# SD_USB_FMU_REV_1A.net
KiCad netlist of a schematic drawn in Altium Designer
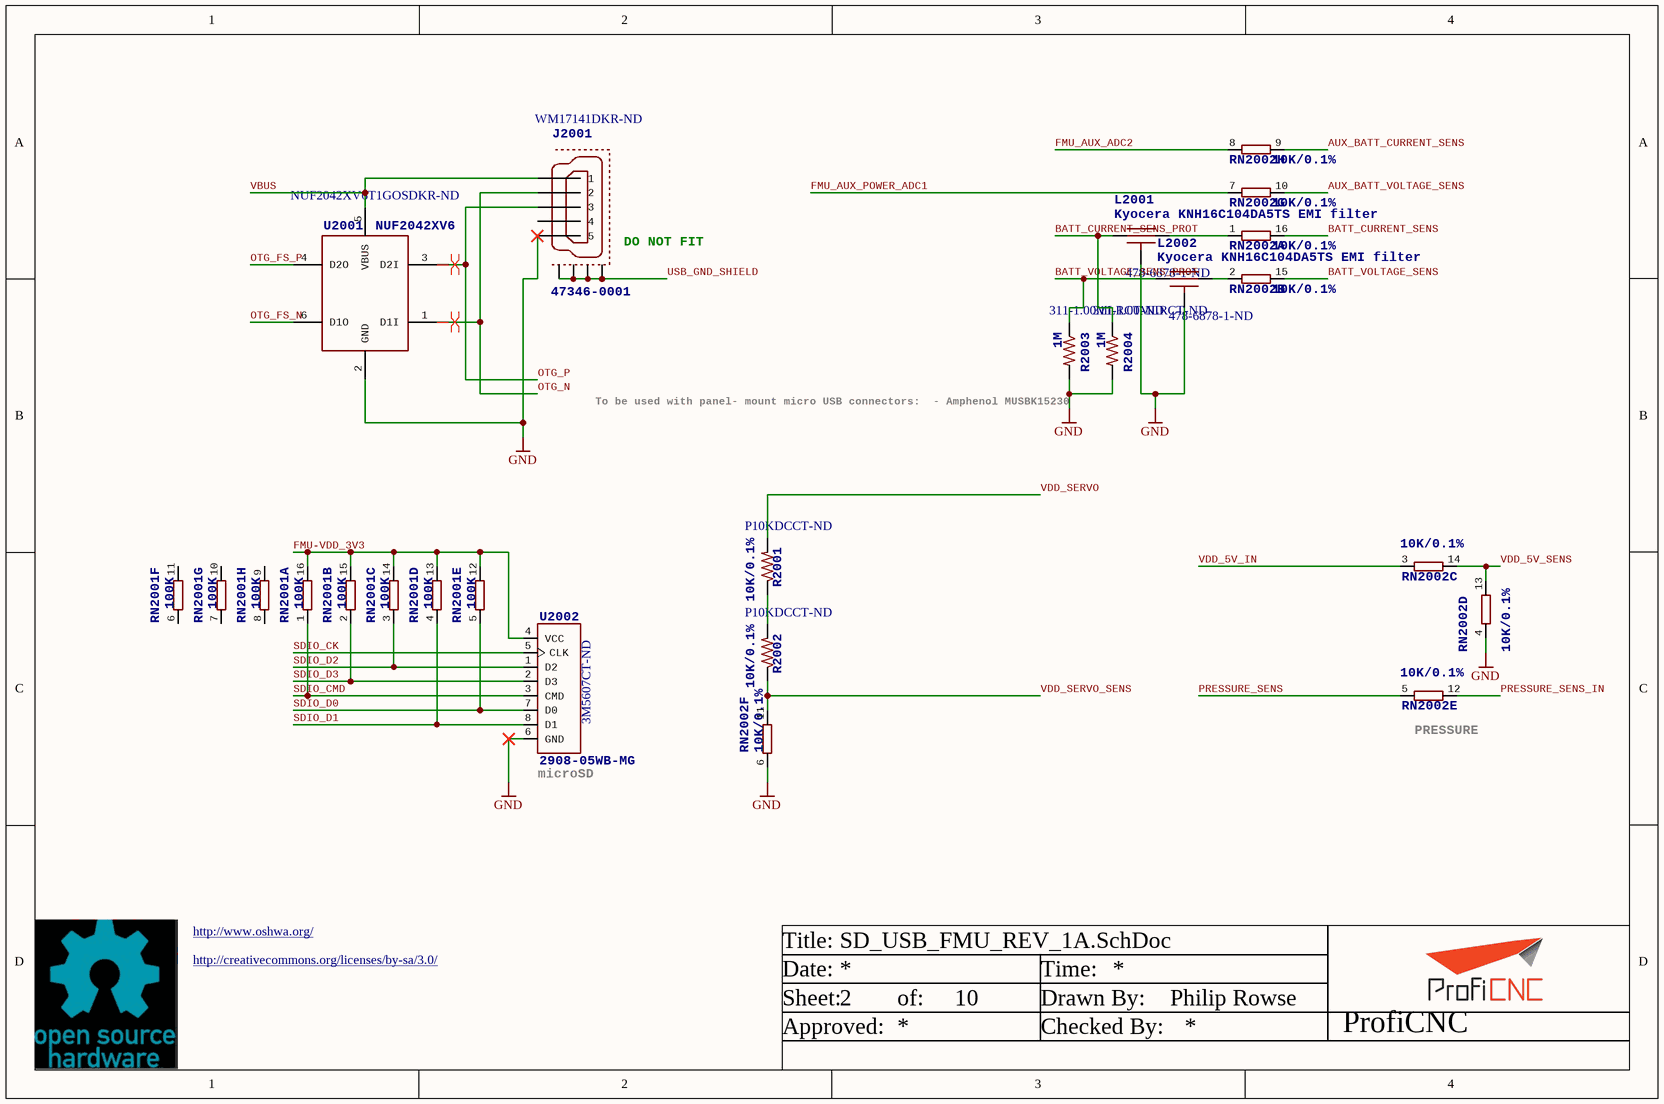
[diagram p0: SD_USB_FMU_REV_1A.SchDoc]

(export (version "E")
  (design (tool "Eeschema 10.0.6"))
  (components
    (comp (ref "J2001")
      (value "47346-0001")
      (footprint "MOLEX-47346-0001")
      (description "MICRO USB B, BOTTOM MOUNT")
      (fields
        (field (name "SUPPLIER PART NUMBER 1") "WM17141DKR-ND")
        (field (name "3DR_PARTNO") "ECM0486")
        (field (name "PARTNO") "0473460001")
      )
      (libsource (lib "pixhawk2") (part "MOLEX-47346-0001"))
    )
    (comp (ref "L2001")
      (value "Kyocera KNH16C104DA5TS EMI filter")
      (footprint "KYOCERA-KNH16-DA")
      (description "FILTER CAP 0.1UF 2A 25V 0603")
      (fields
        (field (name "SUPPLIER PART NUMBER 1") "478-6878-1-ND")
        (field (name "3DR_PARTNO") "ECM0719")
        (field (name "PARTNO") "KNH16C104DA5TS")
      )
      (libsource (lib "pixhawk2") (part "KNH16C104DA5TS"))
    )
    (comp (ref "L2002")
      (value "Kyocera KNH16C104DA5TS EMI filter")
      (footprint "KYOCERA-KNH16-DA")
      (description "FILTER CAP 0.1UF 2A 25V 0603")
      (fields
        (field (name "SUPPLIER PART NUMBER 1") "478-6878-1-ND")
        (field (name "3DR_PARTNO") "ECM0719")
        (field (name "PARTNO") "KNH16C104DA5TS")
      )
      (libsource (lib "pixhawk2") (part "KNH16C104DA5TS"))
    )
    (comp (ref "R2001")
      (value "10K/0.1%")
      (footprint "0402-RES")
      (description "RES 10K OHM 1/16W .1% 0402 SMD")
      (fields
        (field (name "SUPPLIER PART NUMBER 1") "P10KDCCT-ND")
        (field (name "3DR_PARTNO") "ECM0810")
        (field (name "PARTNO") "ERA-2AEB103X")
      )
      (libsource (lib "pixhawk2") (part "RESISTOR0402-RES"))
    )
    (comp (ref "R2002")
      (value "10K/0.1%")
      (footprint "0402-RES")
      (description "RES 10K OHM 1/16W .1% 0402 SMD")
      (fields
        (field (name "SUPPLIER PART NUMBER 1") "P10KDCCT-ND")
        (field (name "3DR_PARTNO") "ECM0810")
        (field (name "PARTNO") "ERA-2AEB103X")
      )
      (libsource (lib "pixhawk2") (part "RESISTOR0402-RES"))
    )
    (comp (ref "R2003")
      (value "1M")
      (footprint "0402-RES")
      (description "RES 1M OHM 1/16W 1% 0402 SMD")
      (fields
        (field (name "PARTNO") "RC0402FR-071ML")
        (field (name "SUPPLIER PART NUMBER 1") "311-1.00MLRCT-ND")
        (field (name "3DR_PARTNO") "ECM0806")
      )
      (libsource (lib "pixhawk2") (part "RESISTOR0402-RES"))
    )
    (comp (ref "R2004")
      (value "1M")
      (footprint "0402-RES")
      (description "RES 1M OHM 1/16W 1% 0402 SMD")
      (fields
        (field (name "PARTNO") "RC0402FR-071ML")
        (field (name "SUPPLIER PART NUMBER 1") "311-1.00MLRCT-ND")
        (field (name "3DR_PARTNO") "ECM0806")
      )
      (libsource (lib "pixhawk2") (part "RESISTOR0402-RES"))
    )
    (comp (ref "RN2001")
      (value "100K")
      (footprint "EXB2HV")
      (description "RES ARRAY 100K OHM 8 RES 1506")
      (fields (field (name "PARTNO") "EXB-2HV104JV") (field (name "3DR_PARTNO") "ECM0101"))
      (libsource (lib "pixhawk2") (part "8R-NEXB2HV-100K"))
    )
    (comp (ref "RN2002")
      (value "10K/0.1%")
      (footprint "EXB2HV")
      (description "RES ARRAY 10K OHM 8 RES 1506")
      (fields (field (name "PARTNO") "EXB-2HV103JV") (field (name "3DR_PARTNO") "ECM0546"))
      (libsource (lib "pixhawk2") (part "8R-NEXB2HV-10K"))
    )
    (comp (ref "U2001")
      (value "NUF2042XV6")
      (footprint "SOT563-6")
      (description "IC FILTER USB ESD PROTECT SOT363")
      (fields
        (field (name "PARTNO") "NUF2042XV6T1G")
        (field (name "SUPPLIER PART NUMBER 1") "NUF2042XV6T1GOSDKR-ND")
        (field (name "3DR_PARTNO") "ECM0836")
      )
      (libsource (lib "pixhawk2") (part "NUF2042XV6"))
    )
    (comp (ref "U2002")
      (value "2908-05WB-MG")
      (footprint "MICROSD")
      (description "CONN MICRO SD CARD PUSH-PUSH R/A")
      (fields (field (name "SUPPLIER PART NUMBER 1") "3M5607CT-ND") (field (name "3DR_PARTNO") "ECM0485"))
      (libsource (lib "baseboard") (part "MICROSDSDI"))
    )
  )
  (nets
    (net (code "1") (name "/AUX_BATT_CURRENT_SENS") (class "Default")
      (node (ref "RN2002") (pin "9") (pinfunction "2_9") (pintype "passive"))
    )
    (net (code "2") (name "/AUX_BATT_VOLTAGE_SENS") (class "Default")
      (node (ref "RN2002") (pin "10") (pinfunction "2_10") (pintype "passive"))
    )
    (net (code "3") (name "/BATT_CURRENT_SENS") (class "Default")
      (node (ref "RN2002") (pin "16") (pinfunction "2_16") (pintype "passive"))
    )
    (net (code "4") (name "/BATT_CURRENT_SENS_PROT") (class "Default")
      (node (ref "L2001") (pin "P$1") (pinfunction "P$1_P$1") (pintype "passive"))
      (node (ref "R2004") (pin "P$1") (pinfunction "1_P$1") (pintype "passive"))
    )
    (net (code "5") (name "/BATT_VOLTAGE_SENS") (class "Default")
      (node (ref "RN2002") (pin "15") (pinfunction "2_15") (pintype "passive"))
    )
    (net (code "6") (name "/BATT_VOLTAGE_SENS_PROT") (class "Default")
      (node (ref "L2002") (pin "P$1") (pinfunction "P$1_P$1") (pintype "passive"))
      (node (ref "R2003") (pin "P$1") (pinfunction "1_P$1") (pintype "passive"))
    )
    (net (code "7") (name "/FMU-VDD_3V3") (class "Default")
      (node (ref "RN2001") (pin "12") (pinfunction "2_12") (pintype "passive"))
      (node (ref "RN2001") (pin "13") (pinfunction "2_13") (pintype "passive"))
      (node (ref "RN2001") (pin "14") (pinfunction "2_14") (pintype "passive"))
      (node (ref "RN2001") (pin "15") (pinfunction "2_15") (pintype "passive"))
      (node (ref "RN2001") (pin "16") (pinfunction "2_16") (pintype "passive"))
      (node (ref "U2002") (pin "4") (pinfunction "VCC_4") (pintype "passive"))
    )
    (net (code "8") (name "/FMU_AUX_ADC2") (class "Default")
      (node (ref "RN2002") (pin "8") (pinfunction "1_8") (pintype "passive"))
    )
    (net (code "9") (name "/FMU_AUX_POWER_ADC1") (class "Default")
      (node (ref "RN2002") (pin "7") (pinfunction "1_7") (pintype "passive"))
    )
    (net (code "10") (name "/OTG_FS_N") (class "Default")
      (node (ref "U2001") (pin "6") (pinfunction "D1O_6") (pintype "passive"))
    )
    (net (code "11") (name "/OTG_FS_P") (class "Default")
      (node (ref "U2001") (pin "4") (pinfunction "D2O_4") (pintype "passive"))
    )
    (net (code "12") (name "/OTG_N") (class "Default")
      (node (ref "J2001") (pin "D-") (pinfunction "2_D-") (pintype "passive"))
      (node (ref "U2001") (pin "1") (pinfunction "D1I_1") (pintype "passive"))
    )
    (net (code "13") (name "/OTG_P") (class "Default")
      (node (ref "J2001") (pin "D+") (pinfunction "3_D+") (pintype "passive"))
      (node (ref "U2001") (pin "3") (pinfunction "D2I_3") (pintype "passive"))
    )
    (net (code "14") (name "/PRESSURE_SENS") (class "Default")
      (node (ref "RN2002") (pin "5") (pinfunction "1_5") (pintype "passive"))
    )
    (net (code "15") (name "/PRESSURE_SENS_IN") (class "Default")
      (node (ref "RN2002") (pin "12") (pinfunction "2_12") (pintype "passive"))
    )
    (net (code "16") (name "/SDIO_CK") (class "Default")
      (node (ref "U2002") (pin "5") (pinfunction "CLK_5") (pintype "passive"))
    )
    (net (code "17") (name "/SDIO_CMD") (class "Default")
      (node (ref "RN2001") (pin "1") (pinfunction "1_1") (pintype "passive"))
      (node (ref "U2002") (pin "3") (pinfunction "CMD_3") (pintype "passive"))
    )
    (net (code "18") (name "/SDIO_D0") (class "Default")
      (node (ref "RN2001") (pin "5") (pinfunction "1_5") (pintype "passive"))
      (node (ref "U2002") (pin "7") (pinfunction "D0_7") (pintype "passive"))
    )
    (net (code "19") (name "/SDIO_D1") (class "Default")
      (node (ref "RN2001") (pin "4") (pinfunction "1_4") (pintype "passive"))
      (node (ref "U2002") (pin "8") (pinfunction "D1_8") (pintype "passive"))
    )
    (net (code "20") (name "/SDIO_D2") (class "Default")
      (node (ref "RN2001") (pin "3") (pinfunction "1_3") (pintype "passive"))
      (node (ref "U2002") (pin "1") (pinfunction "D2_1") (pintype "passive"))
    )
    (net (code "21") (name "/SDIO_D3") (class "Default")
      (node (ref "RN2001") (pin "2") (pinfunction "1_2") (pintype "passive"))
      (node (ref "U2002") (pin "2") (pinfunction "D3_2") (pintype "passive"))
    )
    (net (code "22") (name "/USB_GND_SHIELD") (class "Default")
      (node (ref "J2001") (pin "GND1") (pinfunction "GND1_GND1") (pintype "passive"))
      (node (ref "J2001") (pin "GND2") (pinfunction "GND2_GND2") (pintype "passive"))
      (node (ref "J2001") (pin "GND3") (pinfunction "GND3_GND3") (pintype "passive"))
      (node (ref "J2001") (pin "GND4") (pinfunction "GND4_GND4") (pintype "passive"))
    )
    (net (code "23") (name "/VBUS") (class "Default")
      (node (ref "J2001") (pin "VBUS") (pinfunction "1_VBUS") (pintype "open_emitter"))
      (node (ref "U2001") (pin "5") (pinfunction "VBUS_5") (pintype "passive"))
    )
    (net (code "24") (name "/VDD_5V_IN") (class "Default")
      (node (ref "RN2002") (pin "3") (pinfunction "1_3") (pintype "passive"))
    )
    (net (code "25") (name "/VDD_5V_SENS") (class "Default")
      (node (ref "RN2002") (pin "13") (pinfunction "2_13") (pintype "passive"))
      (node (ref "RN2002") (pin "14") (pinfunction "2_14") (pintype "passive"))
    )
    (net (code "26") (name "/VDD_SERVO") (class "Default")
      (node (ref "R2001") (pin "P$2") (pinfunction "2_P$2") (pintype "passive"))
    )
    (net (code "27") (name "/VDD_SERVO_SENS") (class "Default")
      (node (ref "R2002") (pin "P$1") (pinfunction "1_P$1") (pintype "passive"))
      (node (ref "RN2002") (pin "11") (pinfunction "2_11") (pintype "passive"))
    )
    (net (code "28") (name "GND") (class "Default")
      (node (ref "J2001") (pin "GND") (pinfunction "5_GND") (pintype "open_emitter"))
      (node (ref "L2001") (pin "GND") (pinfunction "GND_GND") (pintype "passive"))
      (node (ref "L2002") (pin "GND") (pinfunction "GND_GND") (pintype "passive"))
      (node (ref "R2003") (pin "P$2") (pinfunction "2_P$2") (pintype "passive"))
      (node (ref "R2004") (pin "P$2") (pinfunction "2_P$2") (pintype "passive"))
      (node (ref "RN2002") (pin "4") (pinfunction "1_4") (pintype "passive"))
      (node (ref "RN2002") (pin "6") (pinfunction "1_6") (pintype "passive"))
      (node (ref "U2001") (pin "2") (pinfunction "GND_2") (pintype "passive"))
      (node (ref "U2002") (pin "6") (pinfunction "GND_6") (pintype "open_emitter"))
    )
    (net (code "29") (name "Net-(L2001-PadP$2)") (class "Default")
      (node (ref "L2001") (pin "P$2") (pinfunction "P$2_P$2") (pintype "passive"))
      (node (ref "RN2002") (pin "1") (pinfunction "1_1") (pintype "passive"))
    )
    (net (code "30") (name "Net-(R2001-1)") (class "Default")
      (node (ref "R2001") (pin "P$1") (pinfunction "1_P$1") (pintype "passive"))
      (node (ref "R2002") (pin "P$2") (pinfunction "2_P$2") (pintype "passive"))
    )
    (net (code "31") (name "Net-(RN2002B-1)") (class "Default")
      (node (ref "L2002") (pin "P$2") (pinfunction "P$2_P$2") (pintype "passive"))
      (node (ref "RN2002") (pin "2") (pinfunction "1_2") (pintype "passive"))
    )
    (net (code "32") (name "unconnected-(J2001-4-PadID)") (class "Default")
      (node (ref "J2001") (pin "ID") (pinfunction "4_ID") (pintype "passive"))
    )
    (net (code "33") (name "unconnected-(RN2001F-1-Pad6)") (class "Default")
      (node (ref "RN2001") (pin "6") (pinfunction "1_6") (pintype "passive"))
    )
    (net (code "34") (name "unconnected-(RN2001F-2-Pad11)") (class "Default")
      (node (ref "RN2001") (pin "11") (pinfunction "2_11") (pintype "passive"))
    )
    (net (code "35") (name "unconnected-(RN2001G-1-Pad7)") (class "Default")
      (node (ref "RN2001") (pin "7") (pinfunction "1_7") (pintype "passive"))
    )
    (net (code "36") (name "unconnected-(RN2001G-2-Pad10)") (class "Default")
      (node (ref "RN2001") (pin "10") (pinfunction "2_10") (pintype "passive"))
    )
    (net (code "37") (name "unconnected-(RN2001H-1-Pad8)") (class "Default")
      (node (ref "RN2001") (pin "8") (pinfunction "1_8") (pintype "passive"))
    )
    (net (code "38") (name "unconnected-(RN2001H-2-Pad9)") (class "Default")
      (node (ref "RN2001") (pin "9") (pinfunction "2_9") (pintype "passive"))
    )
  )
)
